# bracelet_go-safe.net
KiCad netlist of a schematic drawn in EAGLE
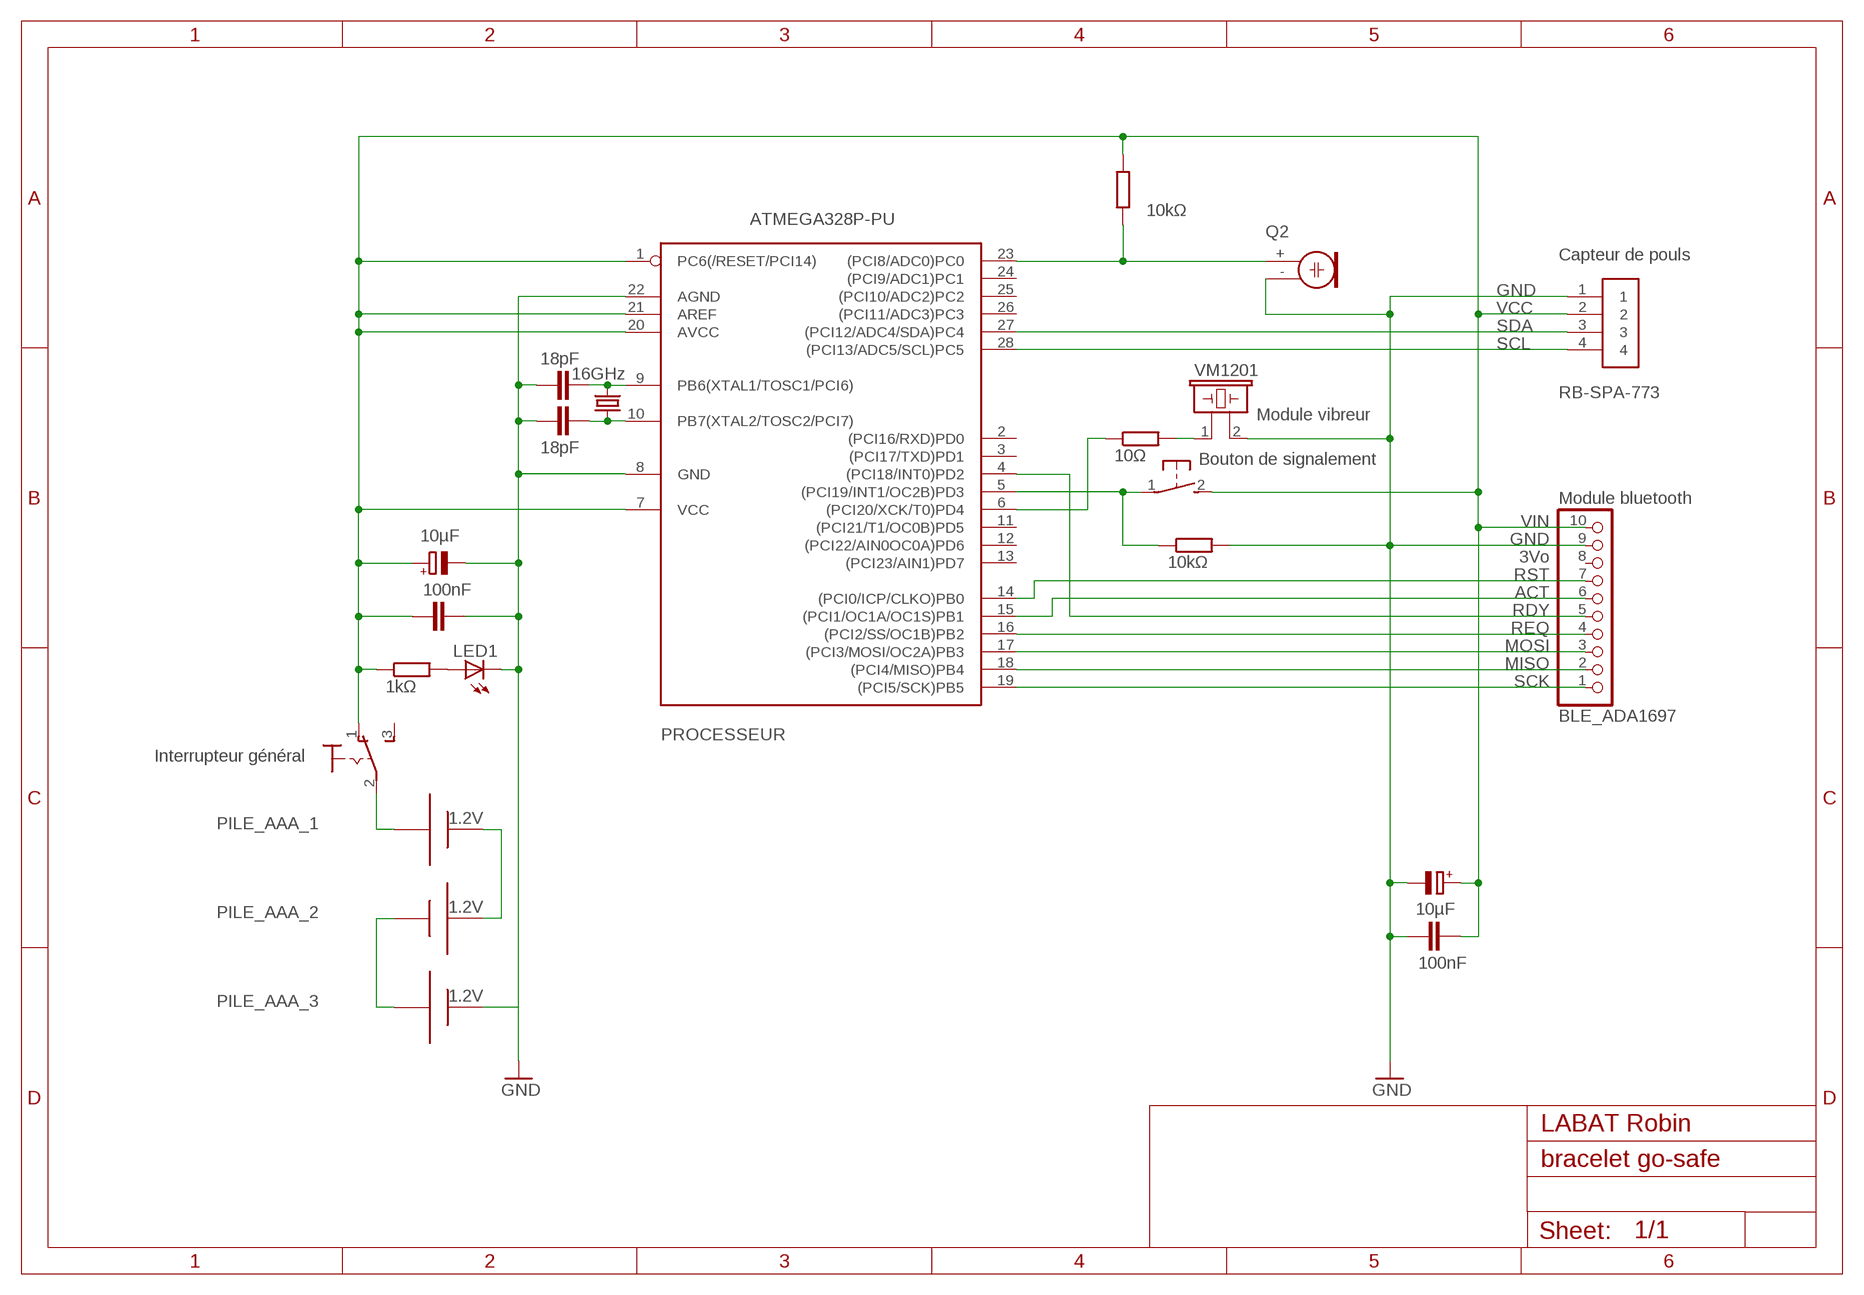
[diagram p0: schematic, sheet 1]

(export (version "E")
  (design (tool "Eeschema 10.0.6"))
  (components
    (comp (ref "BLE_ADA1697")
      (value "Module bluetooth")
      (footprint "eagle-import:1X10-BIG")
      (fields
        (field (name "PIN1") "SCK")
        (field (name "PIN10") "VIN")
        (field (name "PIN2") "MISO")
        (field (name "PIN3") "MOSI")
        (field (name "PIN4") "REQ")
        (field (name "PIN5") "RDY")
        (field (name "PIN6") "ACT")
        (field (name "PIN7") "RST")
        (field (name "PIN8") "3Vo")
        (field (name "PIN9") "GND")
      )
      (libsource (lib "eagle-import") (part "PINHD-1X10"))
    )
    (comp (ref "C1")
      (value "18pF")
      (footprint "eagle-import:C025-024X044")
      (libsource (lib "eagle-import") (part "C-EU025-024X044"))
    )
    (comp (ref "C2")
      (value "18pF")
      (footprint "eagle-import:C025-024X044")
      (libsource (lib "eagle-import") (part "C-EU025-024X044"))
    )
    (comp (ref "C3")
      (value "100nF")
      (footprint "eagle-import:C025-024X044")
      (libsource (lib "eagle-import") (part "C-EU025-024X044"))
    )
    (comp (ref "C4")
      (value "100nF")
      (footprint "eagle-import:C025-024X044")
      (libsource (lib "eagle-import") (part "C-EU025-024X044"))
    )
    (comp (ref "C5")
      (value "10µF")
      (footprint "eagle-import:085CS_1AR")
      (libsource (lib "eagle-import") (part "CPOL-EU085CS-1AR"))
    )
    (comp (ref "C6")
      (value "10µF")
      (footprint "eagle-import:085CS_1AR")
      (libsource (lib "eagle-import") (part "CPOL-EU085CS-1AR"))
    )
    (comp (ref "FRAME1")
      (value "A4L-LOC")
      (footprint "eagle-import:A4L-LOC")
      (libsource (lib "eagle-import") (part "A4L-LOC"))
    )
    (comp (ref "LED1")
      (value "LED")
      (footprint "eagle-import:SMARTLED-TTW")
      (libsource (lib "eagle-import") (part "LED"))
    )
    (comp (ref "PILE_AAA_1")
      (value "AAA")
      (footprint "eagle-import:12BH412")
      (fields (field (name "TENSION") "1.2V"))
      (libsource (lib "eagle-import") (part "AAA"))
    )
    (comp (ref "PILE_AAA_2")
      (value "AAA")
      (footprint "eagle-import:12BH412")
      (fields (field (name "TENSION") "1.2V"))
      (libsource (lib "eagle-import") (part "AAA"))
    )
    (comp (ref "PILE_AAA_3")
      (value "AAA")
      (footprint "eagle-import:12BH412")
      (fields (field (name "TENSION") "1.2V"))
      (libsource (lib "eagle-import") (part "AAA"))
    )
    (comp (ref "PROCESSEUR")
      (value "ATMEGA328P-PU")
      (footprint "eagle-import:DIL28-3")
      (libsource (lib "eagle-import") (part "ATMEGA168PV-10"))
    )
    (comp (ref "Q1")
      (value "16GHz")
      (footprint "eagle-import:86SMX")
      (libsource (lib "eagle-import") (part "CRYSTAL68SMX"))
    )
    (comp (ref "Q2")
      (value "ELECTRET")
      (footprint "eagle-import:9.7ELECTRET")
      (libsource (lib "eagle-import") (part "ELECTRET"))
    )
    (comp (ref "R1")
      (value "10Ω")
      (footprint "eagle-import:0204V")
      (libsource (lib "eagle-import") (part "R-EU_0204/2V"))
    )
    (comp (ref "R2")
      (value "10kΩ")
      (footprint "eagle-import:0204V")
      (libsource (lib "eagle-import") (part "R-EU_0204/2V"))
    )
    (comp (ref "R3")
      (value "1kΩ")
      (footprint "eagle-import:0204V")
      (libsource (lib "eagle-import") (part "R-EU_0204/2V"))
    )
    (comp (ref "R4")
      (value "10kΩ")
      (footprint "eagle-import:0204V")
      (libsource (lib "eagle-import") (part "R-EU_0204/2V"))
    )
    (comp (ref "RB-SPA-773")
      (value "Capteur de pouls")
      (footprint "eagle-import:1X04-3.5MM")
      (fields
        (field (name "PIN1") "GND")
        (field (name "PIN2") "VCC")
        (field (name "PIN3") "SDA")
        (field (name "PIN4") "SCL")
      )
      (libsource (lib "eagle-import") (part "1X4-3.5MM"))
    )
    (comp (ref "S2")
      (value "Bouton de signalement")
      (footprint "eagle-import:B3F-31XX")
      (fields (field (name "MPN") "B3F-3100"))
      (libsource (lib "eagle-import") (part "31-XX"))
    )
    (comp (ref "S3")
      (value "Interrupteur général")
      (footprint "eagle-import:320-916")
      (libsource (lib "eagle-import") (part "320-916"))
    )
    (comp (ref "VM1201")
      (value "Module vibreur")
      (footprint "eagle-import:B_C14S")
      (libsource (lib "eagle-import") (part "B/C14S"))
    )
  )
  (nets
    (net (code "1") (name "GND") (class "Default")
      (node (ref "BLE_ADA1697") (pin "9") (pinfunction "9_9") (pintype "passive"))
      (node (ref "C1") (pin "1") (pinfunction "1_1") (pintype "passive"))
      (node (ref "C2") (pin "1") (pinfunction "1_1") (pintype "passive"))
      (node (ref "C3") (pin "2") (pinfunction "2_2") (pintype "passive"))
      (node (ref "C4") (pin "2") (pinfunction "2_2") (pintype "passive"))
      (node (ref "C5") (pin "-") (pinfunction "-_-") (pintype "passive"))
      (node (ref "C6") (pin "-") (pinfunction "-_-") (pintype "passive"))
      (node (ref "LED1") (pin "C@1") (pinfunction "C_C@1") (pintype "passive"))
      (node (ref "PILE_AAA_3") (pin "+") (pinfunction "+_+") (pintype "bidirectional"))
      (node (ref "PROCESSEUR") (pin "22") (pinfunction "AGND_22") (pintype "bidirectional"))
      (node (ref "PROCESSEUR") (pin "8") (pinfunction "GND_8") (pintype "bidirectional"))
      (node (ref "Q2") (pin "-") (pinfunction "1_-") (pintype "passive"))
      (node (ref "R2") (pin "2") (pinfunction "2_2") (pintype "passive"))
      (node (ref "RB-SPA-773") (pin "1") (pinfunction "1_1") (pintype "bidirectional"))
      (node (ref "VM1201") (pin "2") (pinfunction "2_2") (pintype "passive"))
    )
    (net (code "2") (name "Net-(LED1-A)") (class "Default")
      (node (ref "LED1") (pin "A@1") (pinfunction "A_A@1") (pintype "passive"))
      (node (ref "R3") (pin "2") (pinfunction "2_2") (pintype "passive"))
    )
    (net (code "3") (name "Net-(PILE_AAA_1-Pad+)") (class "Default")
      (node (ref "PILE_AAA_1") (pin "+") (pinfunction "+_+") (pintype "bidirectional"))
      (node (ref "PILE_AAA_2") (pin "-") (pinfunction "-_-") (pintype "bidirectional"))
    )
    (net (code "4") (name "Net-(PILE_AAA_2-Pad+)") (class "Default")
      (node (ref "PILE_AAA_2") (pin "+") (pinfunction "+_+") (pintype "bidirectional"))
      (node (ref "PILE_AAA_3") (pin "-") (pinfunction "-_-") (pintype "bidirectional"))
    )
    (net (code "5") (name "Net-(PROCESSEUR-(PCI0{slash}ICP{slash}CLKO)PB0)") (class "Default")
      (node (ref "BLE_ADA1697") (pin "7") (pinfunction "7_7") (pintype "passive"))
      (node (ref "PROCESSEUR") (pin "14") (pinfunction "(PCI0/ICP/CLKO)PB0_14") (pintype "bidirectional"))
    )
    (net (code "6") (name "Net-(PROCESSEUR-(PCI1{slash}OC1A{slash}OC1S)PB1)") (class "Default")
      (node (ref "BLE_ADA1697") (pin "6") (pinfunction "6_6") (pintype "passive"))
      (node (ref "PROCESSEUR") (pin "15") (pinfunction "(PCI1/OC1A/OC1S)PB1_15") (pintype "bidirectional"))
    )
    (net (code "7") (name "Net-(PROCESSEUR-(PCI2{slash}SS{slash}OC1B)PB2)") (class "Default")
      (node (ref "BLE_ADA1697") (pin "4") (pinfunction "4_4") (pintype "passive"))
      (node (ref "PROCESSEUR") (pin "16") (pinfunction "(PCI2/SS/OC1B)PB2_16") (pintype "bidirectional"))
    )
    (net (code "8") (name "Net-(PROCESSEUR-(PCI3{slash}MOSI{slash}OC2A)PB3)") (class "Default")
      (node (ref "BLE_ADA1697") (pin "3") (pinfunction "3_3") (pintype "passive"))
      (node (ref "PROCESSEUR") (pin "17") (pinfunction "(PCI3/MOSI/OC2A)PB3_17") (pintype "bidirectional"))
    )
    (net (code "9") (name "Net-(PROCESSEUR-(PCI4{slash}MISO)PB4)") (class "Default")
      (node (ref "BLE_ADA1697") (pin "2") (pinfunction "2_2") (pintype "passive"))
      (node (ref "PROCESSEUR") (pin "18") (pinfunction "(PCI4/MISO)PB4_18") (pintype "bidirectional"))
    )
    (net (code "10") (name "Net-(PROCESSEUR-(PCI5{slash}SCK)PB5)") (class "Default")
      (node (ref "BLE_ADA1697") (pin "1") (pinfunction "1_1") (pintype "passive"))
      (node (ref "PROCESSEUR") (pin "19") (pinfunction "(PCI5/SCK)PB5_19") (pintype "bidirectional"))
    )
    (net (code "11") (name "Net-(PROCESSEUR-(PCI8{slash}ADC0)PC0)") (class "Default")
      (node (ref "PROCESSEUR") (pin "23") (pinfunction "(PCI8/ADC0)PC0_23") (pintype "bidirectional"))
      (node (ref "Q2") (pin "+") (pinfunction "2_+") (pintype "passive"))
      (node (ref "R4") (pin "1") (pinfunction "1_1") (pintype "passive"))
    )
    (net (code "12") (name "Net-(PROCESSEUR-(PCI12{slash}ADC4{slash}SDA)PC4)") (class "Default")
      (node (ref "PROCESSEUR") (pin "27") (pinfunction "(PCI12/ADC4/SDA)PC4_27") (pintype "bidirectional"))
      (node (ref "RB-SPA-773") (pin "3") (pinfunction "3_3") (pintype "bidirectional"))
    )
    (net (code "13") (name "Net-(PROCESSEUR-(PCI13{slash}ADC5{slash}SCL)PC5)") (class "Default")
      (node (ref "PROCESSEUR") (pin "28") (pinfunction "(PCI13/ADC5/SCL)PC5_28") (pintype "bidirectional"))
      (node (ref "RB-SPA-773") (pin "4") (pinfunction "4_4") (pintype "bidirectional"))
    )
    (net (code "14") (name "Net-(PROCESSEUR-(PCI18{slash}INT0)PD2)") (class "Default")
      (node (ref "BLE_ADA1697") (pin "5") (pinfunction "5_5") (pintype "passive"))
      (node (ref "PROCESSEUR") (pin "4") (pinfunction "(PCI18/INT0)PD2_4") (pintype "bidirectional"))
    )
    (net (code "15") (name "Net-(PROCESSEUR-(PCI19{slash}INT1{slash}OC2B)PD3)") (class "Default")
      (node (ref "PROCESSEUR") (pin "5") (pinfunction "(PCI19/INT1/OC2B)PD3_5") (pintype "bidirectional"))
      (node (ref "R2") (pin "1") (pinfunction "1_1") (pintype "passive"))
      (node (ref "S2") (pin "1") (pinfunction "P_1") (pintype "passive"))
    )
    (net (code "16") (name "Net-(PROCESSEUR-(PCI20{slash}XCK{slash}T0)PD4)") (class "Default")
      (node (ref "PROCESSEUR") (pin "6") (pinfunction "(PCI20/XCK/T0)PD4_6") (pintype "bidirectional"))
      (node (ref "R1") (pin "1") (pinfunction "1_1") (pintype "passive"))
    )
    (net (code "17") (name "Net-(PROCESSEUR-AREF)") (class "Default")
      (node (ref "BLE_ADA1697") (pin "10") (pinfunction "10_10") (pintype "passive"))
      (node (ref "C3") (pin "1") (pinfunction "1_1") (pintype "passive"))
      (node (ref "C4") (pin "1") (pinfunction "1_1") (pintype "passive"))
      (node (ref "C5") (pin "+") (pinfunction "+_+") (pintype "passive"))
      (node (ref "C6") (pin "+") (pinfunction "+_+") (pintype "passive"))
      (node (ref "PROCESSEUR") (pin "1") (pinfunction "PC6(/RESET/PCI14)_1") (pintype "bidirectional"))
      (node (ref "PROCESSEUR") (pin "20") (pinfunction "AVCC_20") (pintype "bidirectional"))
      (node (ref "PROCESSEUR") (pin "21") (pinfunction "AREF_21") (pintype "bidirectional"))
      (node (ref "PROCESSEUR") (pin "7") (pinfunction "VCC_7") (pintype "bidirectional"))
      (node (ref "R3") (pin "1") (pinfunction "1_1") (pintype "passive"))
      (node (ref "R4") (pin "2") (pinfunction "2_2") (pintype "passive"))
      (node (ref "RB-SPA-773") (pin "2") (pinfunction "2_2") (pintype "bidirectional"))
      (node (ref "S2") (pin "2") (pinfunction "S_2") (pintype "passive"))
      (node (ref "S3") (pin "1") (pinfunction "O_1") (pintype "passive"))
    )
    (net (code "18") (name "Net-(PROCESSEUR-PB6(XTAL1{slash}TOSC1{slash}PCI6))") (class "Default")
      (node (ref "C1") (pin "2") (pinfunction "2_2") (pintype "passive"))
      (node (ref "PROCESSEUR") (pin "9") (pinfunction "PB6(XTAL1/TOSC1/PCI6)_9") (pintype "bidirectional"))
      (node (ref "Q1") (pin "4") (pinfunction "2_4") (pintype "passive"))
    )
    (net (code "19") (name "Net-(PROCESSEUR-PB7(XTAL2{slash}TOSC2{slash}PCI7))") (class "Default")
      (node (ref "C2") (pin "2") (pinfunction "2_2") (pintype "passive"))
      (node (ref "PROCESSEUR") (pin "10") (pinfunction "PB7(XTAL2/TOSC2/PCI7)_10") (pintype "bidirectional"))
      (node (ref "Q1") (pin "1") (pinfunction "1_1") (pintype "passive"))
    )
    (net (code "20") (name "Net-(R1-Pad2)") (class "Default")
      (node (ref "R1") (pin "2") (pinfunction "2_2") (pintype "passive"))
      (node (ref "VM1201") (pin "1") (pinfunction "1_1") (pintype "passive"))
    )
    (net (code "21") (name "Net-(S3-P)") (class "Default")
      (node (ref "PILE_AAA_1") (pin "-") (pinfunction "-_-") (pintype "bidirectional"))
      (node (ref "S3") (pin "2") (pinfunction "P_2") (pintype "passive"))
    )
    (net (code "22") (name "unconnected-(BLE_ADA1697-Pad8)") (class "Default")
      (node (ref "BLE_ADA1697") (pin "8") (pinfunction "8_8") (pintype "passive"))
    )
    (net (code "23") (name "unconnected-(PROCESSEUR-(PCI9{slash}ADC1)PC1-Pad24)") (class "Default")
      (node (ref "PROCESSEUR") (pin "24") (pinfunction "(PCI9/ADC1)PC1_24") (pintype "bidirectional"))
    )
    (net (code "24") (name "unconnected-(PROCESSEUR-(PCI10{slash}ADC2)PC2-Pad25)") (class "Default")
      (node (ref "PROCESSEUR") (pin "25") (pinfunction "(PCI10/ADC2)PC2_25") (pintype "bidirectional"))
    )
    (net (code "25") (name "unconnected-(PROCESSEUR-(PCI11{slash}ADC3)PC3-Pad26)") (class "Default")
      (node (ref "PROCESSEUR") (pin "26") (pinfunction "(PCI11/ADC3)PC3_26") (pintype "bidirectional"))
    )
    (net (code "26") (name "unconnected-(PROCESSEUR-(PCI16{slash}RXD)PD0-Pad2)") (class "Default")
      (node (ref "PROCESSEUR") (pin "2") (pinfunction "(PCI16/RXD)PD0_2") (pintype "bidirectional"))
    )
    (net (code "27") (name "unconnected-(PROCESSEUR-(PCI17{slash}TXD)PD1-Pad3)") (class "Default")
      (node (ref "PROCESSEUR") (pin "3") (pinfunction "(PCI17/TXD)PD1_3") (pintype "bidirectional"))
    )
    (net (code "28") (name "unconnected-(PROCESSEUR-(PCI21{slash}T1{slash}OC0B)PD5-Pad11)") (class "Default")
      (node (ref "PROCESSEUR") (pin "11") (pinfunction "(PCI21/T1/OC0B)PD5_11") (pintype "bidirectional"))
    )
    (net (code "29") (name "unconnected-(PROCESSEUR-(PCI22{slash}AIN0OC0A)PD6-Pad12)") (class "Default")
      (node (ref "PROCESSEUR") (pin "12") (pinfunction "(PCI22/AIN0OC0A)PD6_12") (pintype "bidirectional"))
    )
    (net (code "30") (name "unconnected-(PROCESSEUR-(PCI23{slash}AIN1)PD7-Pad13)") (class "Default")
      (node (ref "PROCESSEUR") (pin "13") (pinfunction "(PCI23/AIN1)PD7_13") (pintype "bidirectional"))
    )
    (net (code "31") (name "unconnected-(S3-S-Pad3)") (class "Default")
      (node (ref "S3") (pin "3") (pinfunction "S_3") (pintype "passive"))
    )
  )
)
